# ltc2400_adc_module.net
KiCad netlist of a schematic drawn in EAGLE
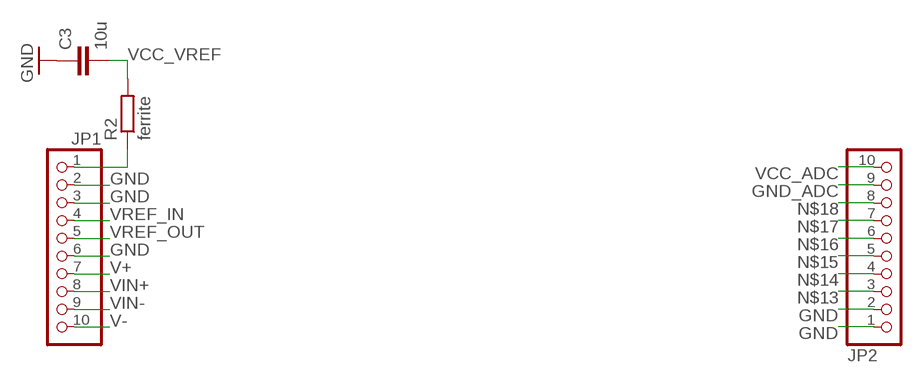
[diagram p0: schematic, sheet 1]

(export (version "E")
  (design (tool "Eeschema 10.0.6"))
  (components
    (comp (ref "C3")
      (value "10u")
      (footprint "eagle-import:C0805")
      (libsource (lib "eagle-import") (part "C-EUC0805"))
    )
    (comp (ref "JP1")
      (value "PINHD-1X10NORM_OCT")
      (footprint "eagle-import:1X10_NORMAL_OCT")
      (libsource (lib "eagle-import") (part "PINHD-1X10NORM_OCT"))
    )
    (comp (ref "JP2")
      (value "PINHD-1X10NORM_OCT")
      (footprint "eagle-import:1X10_NORMAL_OCT")
      (libsource (lib "eagle-import") (part "PINHD-1X10NORM_OCT"))
    )
    (comp (ref "R2")
      (value "ferrite")
      (footprint "eagle-import:R0805")
      (libsource (lib "eagle-import") (part "R-EU_R0805"))
    )
  )
  (nets
    (net (code "1") (name "/GND_ADC") (class "Default")
      (node (ref "JP2") (pin "9") (pinfunction "9_9") (pintype "passive"))
    )
    (net (code "2") (name "/N$13") (class "Default")
      (node (ref "JP2") (pin "3") (pinfunction "3_3") (pintype "passive"))
    )
    (net (code "3") (name "/N$14") (class "Default")
      (node (ref "JP2") (pin "4") (pinfunction "4_4") (pintype "passive"))
    )
    (net (code "4") (name "/N$15") (class "Default")
      (node (ref "JP2") (pin "5") (pinfunction "5_5") (pintype "passive"))
    )
    (net (code "5") (name "/N$16") (class "Default")
      (node (ref "JP2") (pin "6") (pinfunction "6_6") (pintype "passive"))
    )
    (net (code "6") (name "/N$17") (class "Default")
      (node (ref "JP2") (pin "7") (pinfunction "7_7") (pintype "passive"))
    )
    (net (code "7") (name "/N$18") (class "Default")
      (node (ref "JP2") (pin "8") (pinfunction "8_8") (pintype "passive"))
    )
    (net (code "8") (name "/V+") (class "Default")
      (node (ref "JP1") (pin "7") (pinfunction "7_7") (pintype "passive"))
    )
    (net (code "9") (name "/V-") (class "Default")
      (node (ref "JP1") (pin "10") (pinfunction "10_10") (pintype "passive"))
    )
    (net (code "10") (name "/VCC_ADC") (class "Default")
      (node (ref "JP2") (pin "10") (pinfunction "10_10") (pintype "passive"))
    )
    (net (code "11") (name "/VCC_VREF") (class "Default")
      (node (ref "C3") (pin "2") (pinfunction "2_2") (pintype "passive"))
      (node (ref "R2") (pin "2") (pinfunction "2_2") (pintype "passive"))
    )
    (net (code "12") (name "/VIN+") (class "Default")
      (node (ref "JP1") (pin "8") (pinfunction "8_8") (pintype "passive"))
    )
    (net (code "13") (name "/VIN-") (class "Default")
      (node (ref "JP1") (pin "9") (pinfunction "9_9") (pintype "passive"))
    )
    (net (code "14") (name "/VREF_IN") (class "Default")
      (node (ref "JP1") (pin "4") (pinfunction "4_4") (pintype "passive"))
    )
    (net (code "15") (name "/VREF_OUT") (class "Default")
      (node (ref "JP1") (pin "5") (pinfunction "5_5") (pintype "passive"))
    )
    (net (code "16") (name "GND") (class "Default")
      (node (ref "C3") (pin "1") (pinfunction "1_1") (pintype "passive"))
      (node (ref "JP1") (pin "2") (pinfunction "2_2") (pintype "passive"))
      (node (ref "JP1") (pin "3") (pinfunction "3_3") (pintype "passive"))
      (node (ref "JP1") (pin "6") (pinfunction "6_6") (pintype "passive"))
      (node (ref "JP2") (pin "1") (pinfunction "1_1") (pintype "passive"))
      (node (ref "JP2") (pin "2") (pinfunction "2_2") (pintype "passive"))
    )
    (net (code "17") (name "Net-(JP1-Pad1)") (class "Default")
      (node (ref "JP1") (pin "1") (pinfunction "1_1") (pintype "passive"))
      (node (ref "R2") (pin "1") (pinfunction "1_1") (pintype "passive"))
    )
  )
)
